# MosfetDriver.net
KiCad netlist of a schematic drawn in Altium Designer
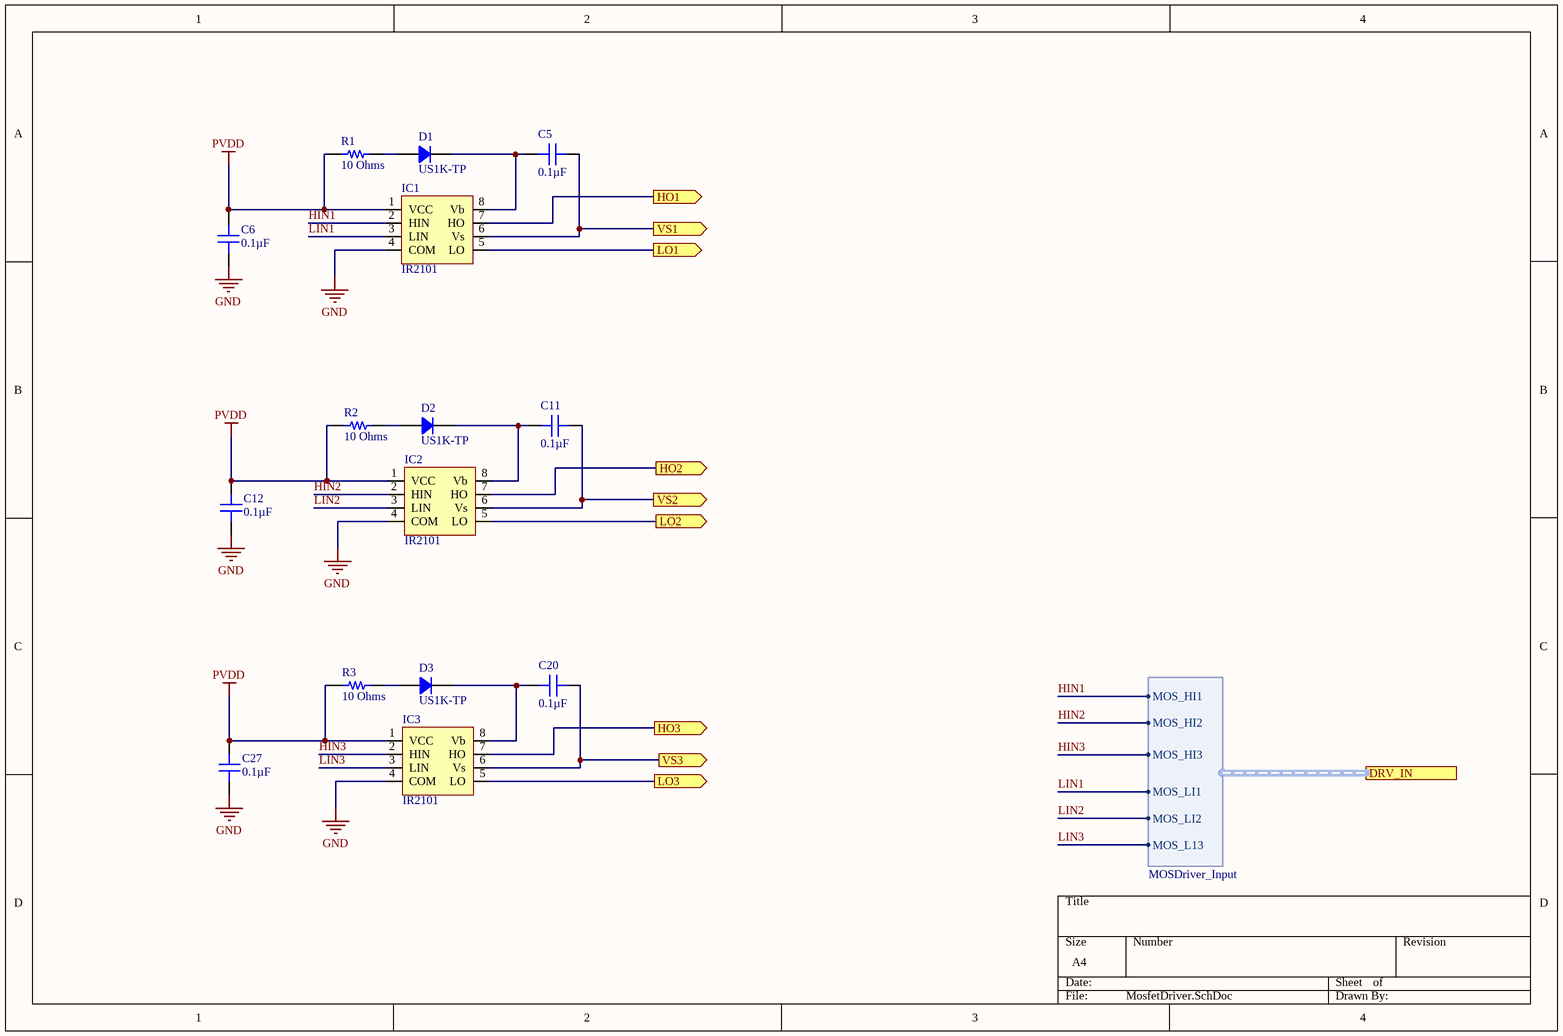
[diagram p0: MosfetDriver.SchDoc]

(export (version "E")
  (design (tool "Eeschema 10.0.6"))
  (components
    (comp (ref "C5")
      (value "0.1µF")
      (footprint "CAP 0805_2012")
      (description "CAP CER 0.1UF 50V X7R 0805")
      (fields
        (field (name "PART NUMBER") "CML0805X7R104KT50V")
        (field (name "MANUFACTURER") "Stackpole Electronics Inc")
      )
      (libsource (lib "Celestial Altium Library - altium_library") (part "Capacitor"))
    )
    (comp (ref "C6")
      (value "0.1µF")
      (footprint "CAP 0805_2012")
      (description "CAP CER 0.1UF 50V X7R 0805")
      (fields
        (field (name "PART NUMBER") "CML0805X7R104KT50V")
        (field (name "MANUFACTURER") "Stackpole Electronics Inc")
      )
      (libsource (lib "Celestial Altium Library - altium_library") (part "Capacitor"))
    )
    (comp (ref "C11")
      (value "0.1µF")
      (footprint "CAP 0805_2012")
      (description "CAP CER 0.1UF 50V X7R 0805")
      (fields
        (field (name "PART NUMBER") "CML0805X7R104KT50V")
        (field (name "MANUFACTURER") "Stackpole Electronics Inc")
      )
      (libsource (lib "Celestial Altium Library - altium_library") (part "Capacitor"))
    )
    (comp (ref "C12")
      (value "0.1µF")
      (footprint "CAP 0805_2012")
      (description "CAP CER 0.1UF 50V X7R 0805")
      (fields
        (field (name "PART NUMBER") "CML0805X7R104KT50V")
        (field (name "MANUFACTURER") "Stackpole Electronics Inc")
      )
      (libsource (lib "Celestial Altium Library - altium_library") (part "Capacitor"))
    )
    (comp (ref "C20")
      (value "0.1µF")
      (footprint "CAP 0805_2012")
      (description "CAP CER 0.1UF 50V X7R 0805")
      (fields
        (field (name "PART NUMBER") "CML0805X7R104KT50V")
        (field (name "MANUFACTURER") "Stackpole Electronics Inc")
      )
      (libsource (lib "Celestial Altium Library - altium_library") (part "Capacitor"))
    )
    (comp (ref "C27")
      (value "0.1µF")
      (footprint "CAP 0805_2012")
      (description "CAP CER 0.1UF 50V X7R 0805")
      (fields
        (field (name "PART NUMBER") "CML0805X7R104KT50V")
        (field (name "MANUFACTURER") "Stackpole Electronics Inc")
      )
      (libsource (lib "Celestial Altium Library - altium_library") (part "Capacitor"))
    )
    (comp (ref "D1")
      (value "US1K-TP")
      (footprint "DO214AC SMA")
      (description "DIODE GEN PURP 800V 1A DO214AC")
      (fields (field (name "MANUFACTURER") "Micro Commercial Co"))
      (libsource (lib "Celestial Altium Library - altium_library") (part "Diode"))
    )
    (comp (ref "D2")
      (value "US1K-TP")
      (footprint "DO214AC SMA")
      (description "DIODE GEN PURP 800V 1A DO214AC")
      (fields (field (name "MANUFACTURER") "Micro Commercial Co"))
      (libsource (lib "Celestial Altium Library - altium_library") (part "Diode"))
    )
    (comp (ref "D3")
      (value "US1K-TP")
      (footprint "DO214AC SMA")
      (description "DIODE GEN PURP 800V 1A DO214AC")
      (fields (field (name "MANUFACTURER") "Micro Commercial Co"))
      (libsource (lib "Celestial Altium Library - altium_library") (part "Diode"))
    )
    (comp (ref "IC1")
      (value "IR2101")
      (footprint "SOIC8")
      (description "IC-2101 HIGH-LOW DRIVER SOP8 IR")
      (libsource (lib "UserIntegrated") (part "IR2101"))
    )
    (comp (ref "IC2")
      (value "IR2101")
      (footprint "SOIC8")
      (description "IC-2101 HIGH-LOW DRIVER SOP8 IR")
      (libsource (lib "UserIntegrated") (part "IR2101"))
    )
    (comp (ref "IC3")
      (value "IR2101")
      (footprint "SOIC8")
      (description "IC-2101 HIGH-LOW DRIVER SOP8 IR")
      (libsource (lib "UserIntegrated") (part "IR2101"))
    )
    (comp (ref "R1")
      (value "10 Ohms")
      (footprint "RES 0805_2012")
      (description "RES 10 OHM 1% 1/4W 0805")
      (fields
        (field (name "PART NUMBER") "RK73H2ATTD10R0F")
        (field (name "MANUFACTURER") "KOA Speer Electronics, Inc.")
      )
      (libsource (lib "Celestial Altium Library - altium_library") (part "Resistor"))
    )
    (comp (ref "R2")
      (value "10 Ohms")
      (footprint "RES 0805_2012")
      (description "RES 10 OHM 1% 1/4W 0805")
      (fields
        (field (name "PART NUMBER") "RK73H2ATTD10R0F")
        (field (name "MANUFACTURER") "KOA Speer Electronics, Inc.")
      )
      (libsource (lib "Celestial Altium Library - altium_library") (part "Resistor"))
    )
    (comp (ref "R3")
      (value "10 Ohms")
      (footprint "RES 0805_2012")
      (description "RES 10 OHM 1% 1/4W 0805")
      (fields
        (field (name "PART NUMBER") "RK73H2ATTD10R0F")
        (field (name "MANUFACTURER") "KOA Speer Electronics, Inc.")
      )
      (libsource (lib "Celestial Altium Library - altium_library") (part "Resistor"))
    )
  )
  (nets
    (net (code "2") (name "/HIN1") (class "Default")
      (node (ref "IC1") (pin "2") (pinfunction "HIN_2") (pintype "passive"))
    )
    (net (code "3") (name "/HIN2") (class "Default")
      (node (ref "IC2") (pin "2") (pinfunction "HIN_2") (pintype "passive"))
    )
    (net (code "4") (name "/HIN3") (class "Default")
      (node (ref "IC3") (pin "2") (pinfunction "HIN_2") (pintype "passive"))
    )
    (net (code "5") (name "/HO1") (class "Default")
      (node (ref "IC1") (pin "7") (pinfunction "HO_7") (pintype "passive"))
    )
    (net (code "6") (name "/HO2") (class "Default")
      (node (ref "IC2") (pin "7") (pinfunction "HO_7") (pintype "passive"))
    )
    (net (code "7") (name "/HO3") (class "Default")
      (node (ref "IC3") (pin "7") (pinfunction "HO_7") (pintype "passive"))
    )
    (net (code "8") (name "/LIN1") (class "Default")
      (node (ref "IC1") (pin "3") (pinfunction "LIN_3") (pintype "passive"))
    )
    (net (code "9") (name "/LIN2") (class "Default")
      (node (ref "IC2") (pin "3") (pinfunction "LIN_3") (pintype "passive"))
    )
    (net (code "10") (name "/LIN3") (class "Default")
      (node (ref "IC3") (pin "3") (pinfunction "LIN_3") (pintype "passive"))
    )
    (net (code "11") (name "/LO1") (class "Default")
      (node (ref "IC1") (pin "5") (pinfunction "LO_5") (pintype "passive"))
    )
    (net (code "12") (name "/LO2") (class "Default")
      (node (ref "IC2") (pin "5") (pinfunction "LO_5") (pintype "passive"))
    )
    (net (code "13") (name "/LO3") (class "Default")
      (node (ref "IC3") (pin "5") (pinfunction "LO_5") (pintype "passive"))
    )
    (net (code "14") (name "/VS1") (class "Default")
      (node (ref "C5") (pin "1") (pinfunction "1_1") (pintype "passive"))
      (node (ref "IC1") (pin "6") (pinfunction "Vs_6") (pintype "passive"))
    )
    (net (code "15") (name "/VS2") (class "Default")
      (node (ref "C11") (pin "1") (pinfunction "1_1") (pintype "passive"))
      (node (ref "IC2") (pin "6") (pinfunction "Vs_6") (pintype "passive"))
    )
    (net (code "16") (name "/VS3") (class "Default")
      (node (ref "C20") (pin "1") (pinfunction "1_1") (pintype "passive"))
      (node (ref "IC3") (pin "6") (pinfunction "Vs_6") (pintype "passive"))
    )
    (net (code "18") (name "GND") (class "Default")
      (node (ref "C12") (pin "1") (pinfunction "1_1") (pintype "passive"))
      (node (ref "C27") (pin "1") (pinfunction "1_1") (pintype "passive"))
      (node (ref "C6") (pin "1") (pinfunction "1_1") (pintype "passive"))
      (node (ref "IC1") (pin "4") (pinfunction "COM_4") (pintype "passive"))
      (node (ref "IC2") (pin "4") (pinfunction "COM_4") (pintype "passive"))
      (node (ref "IC3") (pin "4") (pinfunction "COM_4") (pintype "passive"))
    )
    (net (code "19") (name "Net-(D1-Pad1)") (class "Default")
      (node (ref "D1") (pin "1") (pinfunction "1_1") (pintype "passive"))
      (node (ref "R1") (pin "2") (pinfunction "2_2") (pintype "passive"))
    )
    (net (code "20") (name "Net-(D2-Pad1)") (class "Default")
      (node (ref "D2") (pin "1") (pinfunction "1_1") (pintype "passive"))
      (node (ref "R2") (pin "2") (pinfunction "2_2") (pintype "passive"))
    )
    (net (code "21") (name "Net-(D3-Pad1)") (class "Default")
      (node (ref "D3") (pin "1") (pinfunction "1_1") (pintype "passive"))
      (node (ref "R3") (pin "2") (pinfunction "2_2") (pintype "passive"))
    )
    (net (code "22") (name "Net-(IC1-Vb)") (class "Default")
      (node (ref "C5") (pin "2") (pinfunction "2_2") (pintype "passive"))
      (node (ref "D1") (pin "2") (pinfunction "2_2") (pintype "passive"))
      (node (ref "IC1") (pin "8") (pinfunction "Vb_8") (pintype "passive"))
    )
    (net (code "23") (name "Net-(IC2-Vb)") (class "Default")
      (node (ref "C11") (pin "2") (pinfunction "2_2") (pintype "passive"))
      (node (ref "D2") (pin "2") (pinfunction "2_2") (pintype "passive"))
      (node (ref "IC2") (pin "8") (pinfunction "Vb_8") (pintype "passive"))
    )
    (net (code "24") (name "Net-(IC3-Vb)") (class "Default")
      (node (ref "C20") (pin "2") (pinfunction "2_2") (pintype "passive"))
      (node (ref "D3") (pin "2") (pinfunction "2_2") (pintype "passive"))
      (node (ref "IC3") (pin "8") (pinfunction "Vb_8") (pintype "passive"))
    )
    (net (code "25") (name "PVDD") (class "Default")
      (node (ref "C12") (pin "2") (pinfunction "2_2") (pintype "passive"))
      (node (ref "C27") (pin "2") (pinfunction "2_2") (pintype "passive"))
      (node (ref "C6") (pin "2") (pinfunction "2_2") (pintype "passive"))
      (node (ref "IC1") (pin "1") (pinfunction "VCC_1") (pintype "passive"))
      (node (ref "IC2") (pin "1") (pinfunction "VCC_1") (pintype "passive"))
      (node (ref "IC3") (pin "1") (pinfunction "VCC_1") (pintype "passive"))
      (node (ref "R1") (pin "1") (pinfunction "1_1") (pintype "passive"))
      (node (ref "R2") (pin "1") (pinfunction "1_1") (pintype "passive"))
      (node (ref "R3") (pin "1") (pinfunction "1_1") (pintype "passive"))
    )
  )
)
